# STM32H753_PINOUT.net
KiCad netlist of a schematic drawn in Altium Designer
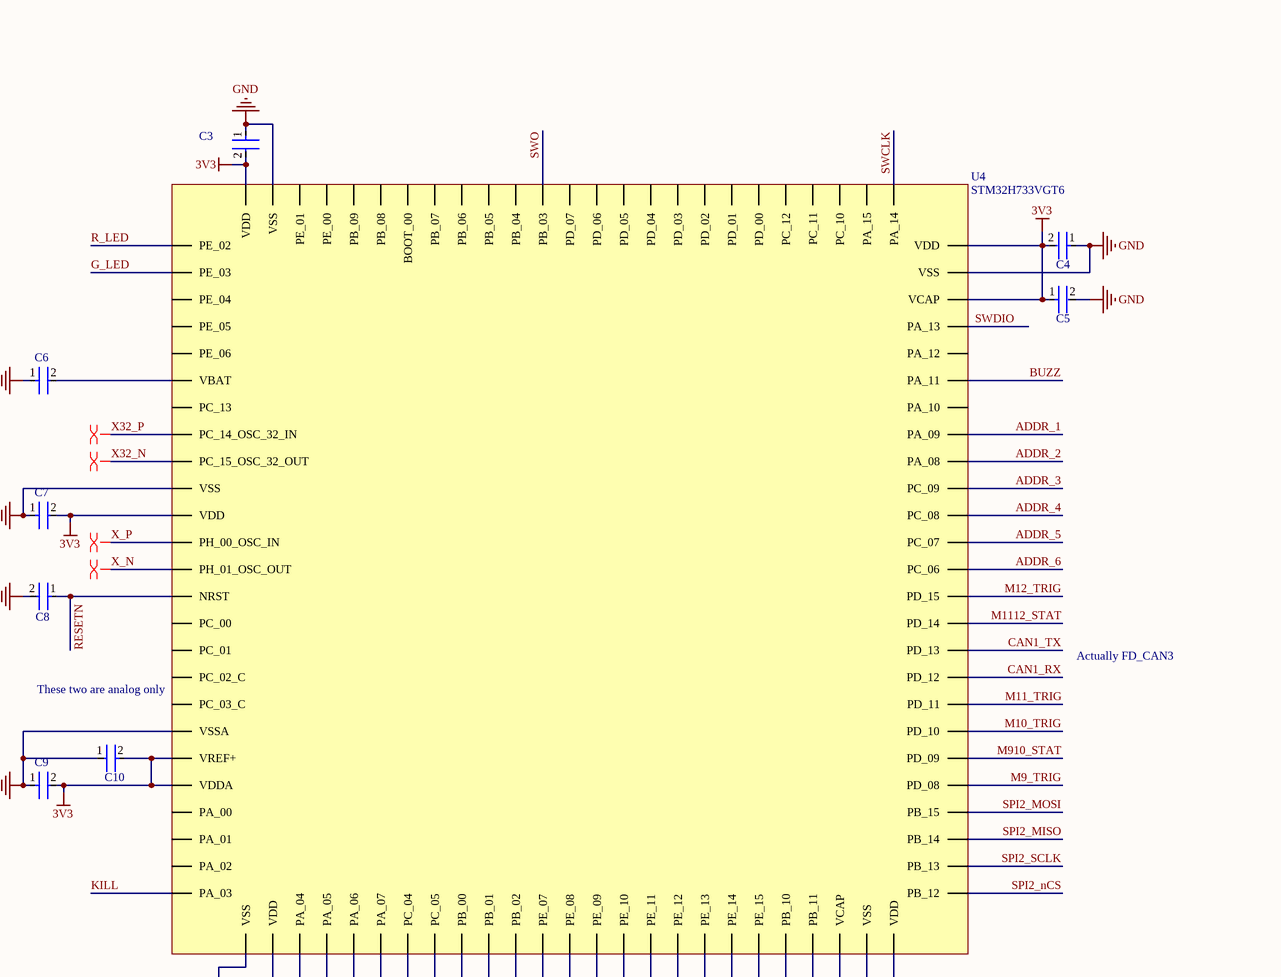
[diagram p0: STM32H753_PINOUT.SchDoc, top middle]
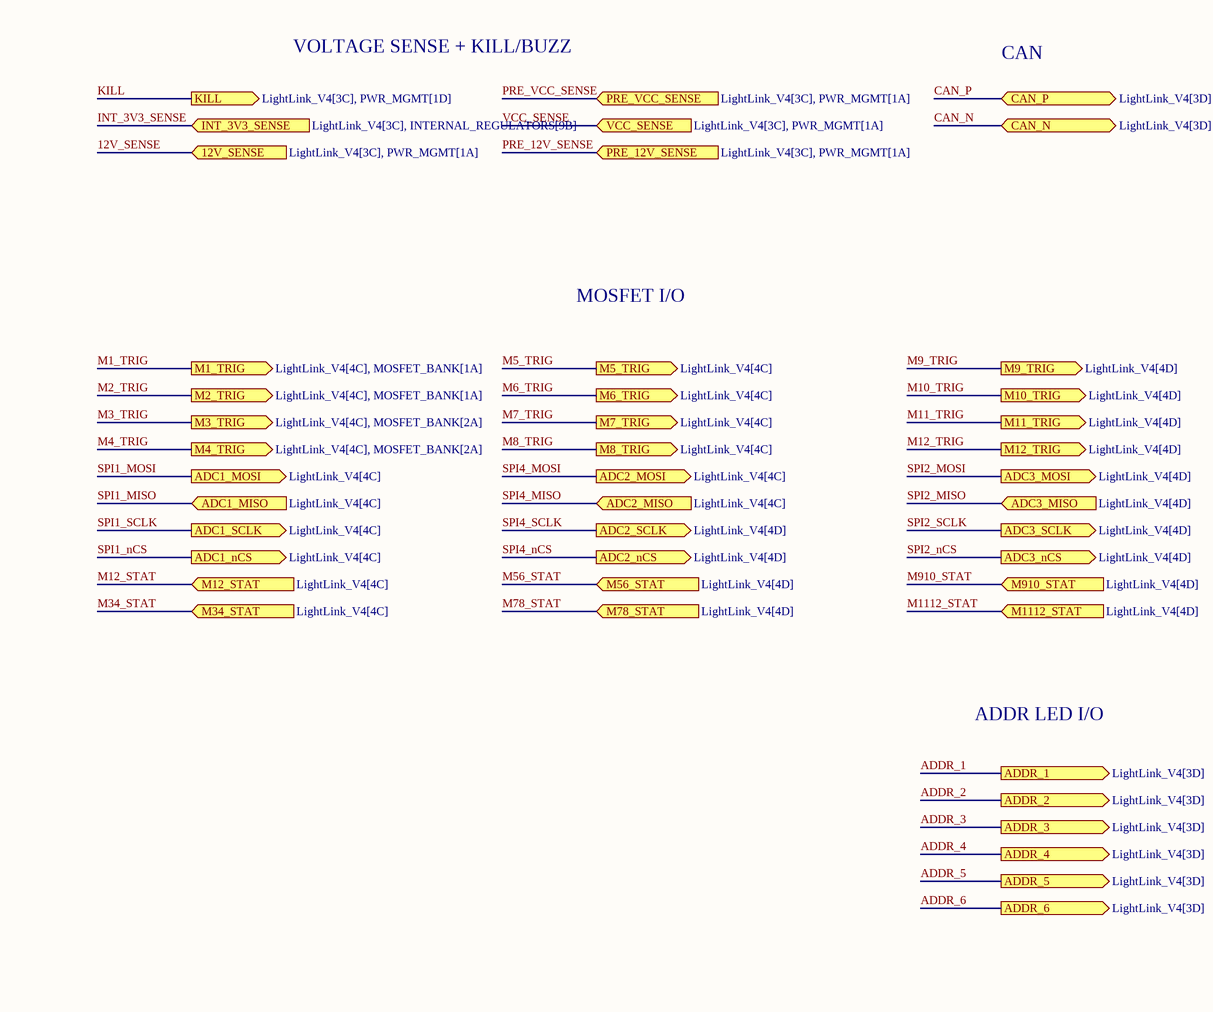
[diagram p1: STM32H753_PINOUT.SchDoc, top right]
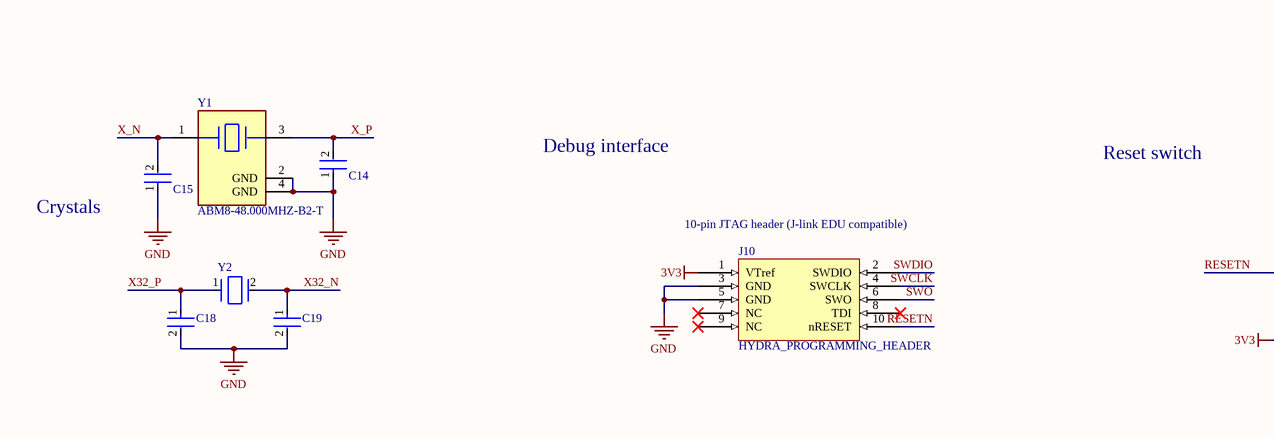
[diagram p2: STM32H753_PINOUT.SchDoc, bottom left]
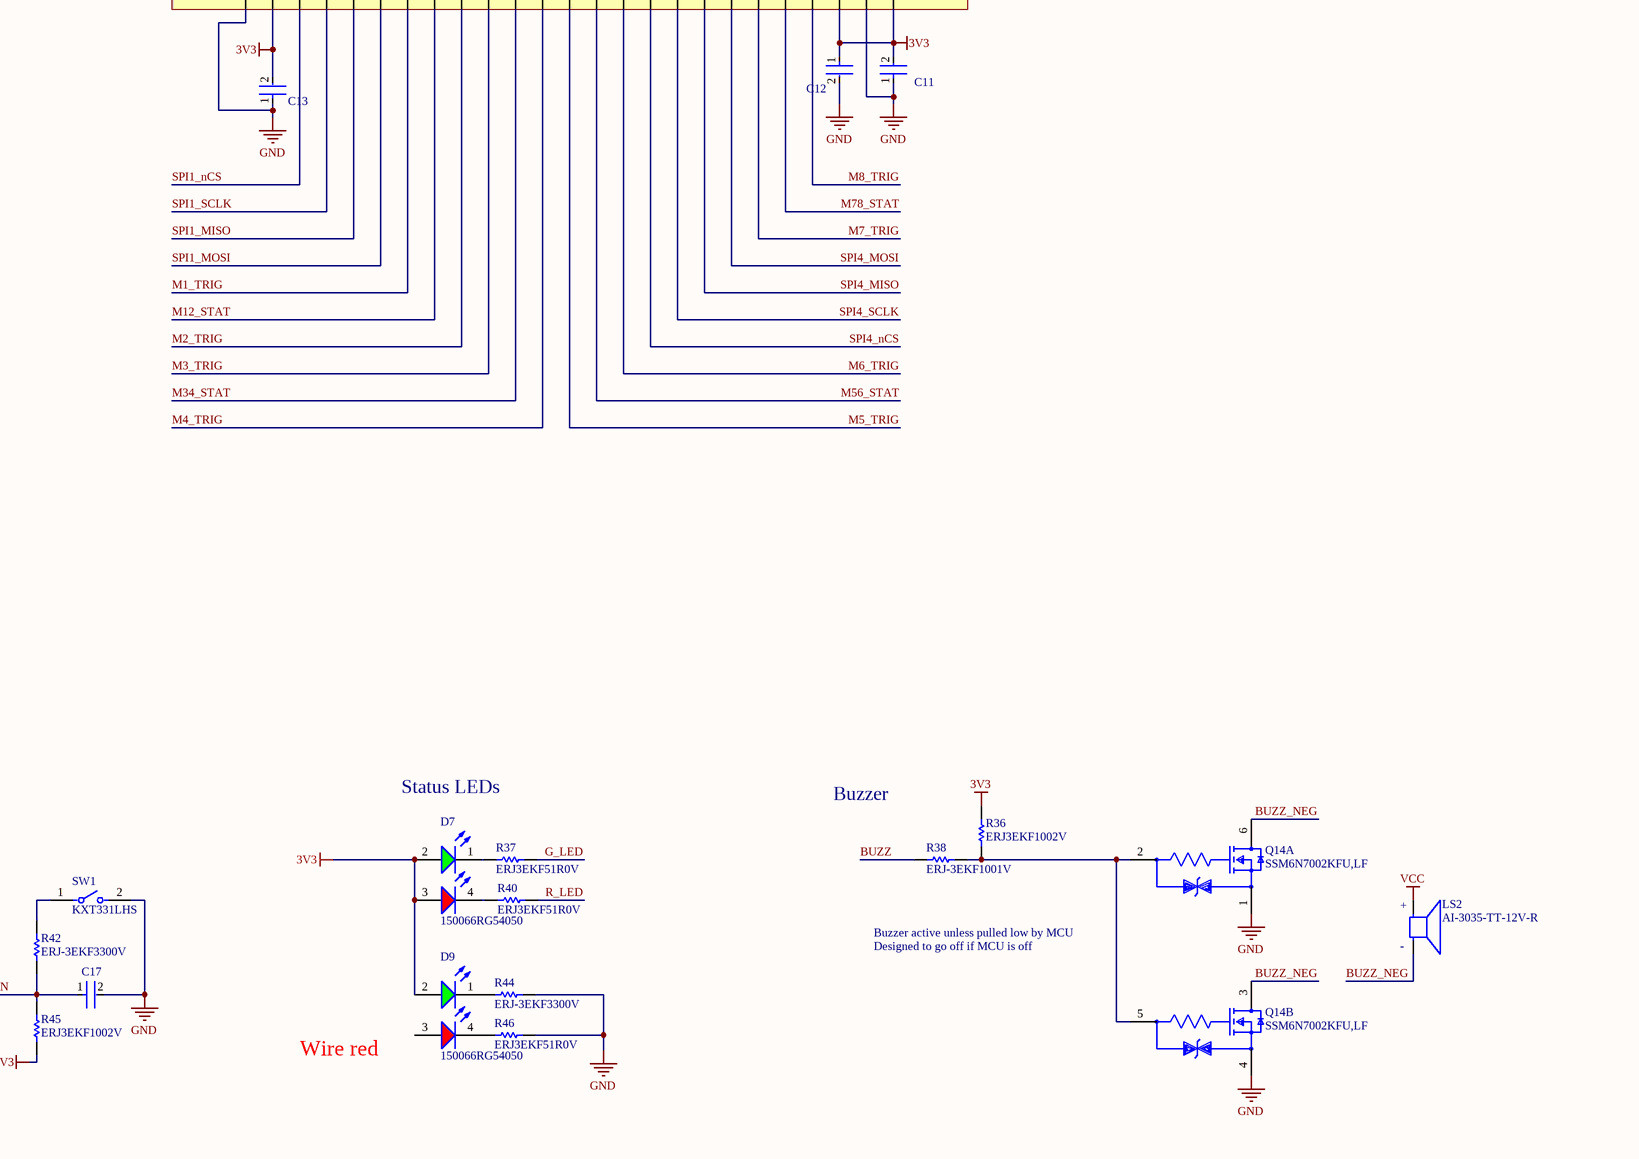
[diagram p3: STM32H753_PINOUT.SchDoc, bottom middle]
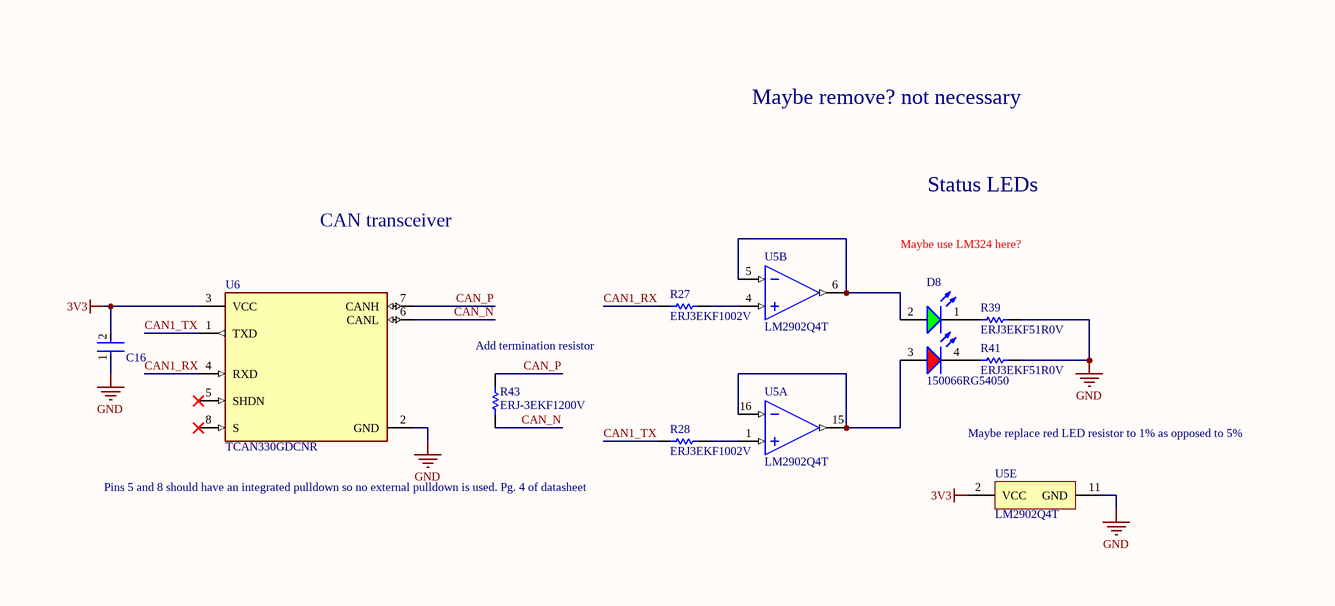
[diagram p4: STM32H753_PINOUT.SchDoc, bottom right]

(export (version "E")
  (design (tool "Eeschema 10.0.6"))
  (components
    (comp (ref "C3")
      (value "C0402C104K8PACTU")
      (footprint "FP-C0402-BB-MFG")
      (fields
        (field (name "MANUFACTURER") "Kemet")
        (field (name "TOLERANCE") "0.1")
        (field (name "OCTOPART") "https://octopart.com/c0402c104k8pactu-kemet-140039")
      )
      (libsource (lib "Altium Content Vault") (part "b4654b650e69147ec39a6b967a45e02"))
    )
    (comp (ref "C4")
      (value "C0402C104K8PACTU")
      (footprint "FP-C0402-BB-MFG")
      (fields
        (field (name "MANUFACTURER") "Kemet")
        (field (name "TOLERANCE") "0.1")
        (field (name "OCTOPART") "https://octopart.com/c0402c104k8pactu-kemet-140039")
      )
      (libsource (lib "Altium Content Vault") (part "b4654b650e69147ec39a6b967a45e02"))
    )
    (comp (ref "C5")
      (value "C1005X7S1A225K050BC")
      (footprint "FP-C1005-050-0_15-0_1-MFG")
      (description "CAP CER 2.2UF 10V X7S 0402")
      (fields (field (name "TOLERANCE") "10%"))
      (libsource (lib "Altium Content Vault") (part "b4654b650e69147ec39a6b967a45e02"))
    )
    (comp (ref "C6")
      (value "C0402C104K8PACTU")
      (footprint "FP-C0402-BB-MFG")
      (fields
        (field (name "MANUFACTURER") "Kemet")
        (field (name "TOLERANCE") "0.1")
        (field (name "OCTOPART") "https://octopart.com/c0402c104k8pactu-kemet-140039")
      )
      (libsource (lib "Altium Content Vault") (part "b4654b650e69147ec39a6b967a45e02"))
    )
    (comp (ref "C7")
      (value "C0402C104K8PACTU")
      (footprint "FP-C0402-BB-MFG")
      (fields
        (field (name "MANUFACTURER") "Kemet")
        (field (name "TOLERANCE") "0.1")
        (field (name "OCTOPART") "https://octopart.com/c0402c104k8pactu-kemet-140039")
      )
      (libsource (lib "Altium Content Vault") (part "b4654b650e69147ec39a6b967a45e02"))
    )
    (comp (ref "C8")
      (value "C0402C104K8PACTU")
      (footprint "FP-C0402-BB-MFG")
      (description "CAP CER 0.1UF 10V X5R 0402")
      (fields (field (name "MANUFACTURER") "Kemet") (field (name "TOLERANCE") "0.1"))
      (libsource (lib "Altium Content Vault") (part "b4654b650e69147ec39a6b967a45e02"))
    )
    (comp (ref "C9")
      (value "C0402C104K8PACTU")
      (footprint "FP-C0402-BB-MFG")
      (fields
        (field (name "MANUFACTURER") "Kemet")
        (field (name "TOLERANCE") "0.1")
        (field (name "OCTOPART") "https://octopart.com/c0402c104k8pactu-kemet-140039")
      )
      (libsource (lib "Altium Content Vault") (part "b4654b650e69147ec39a6b967a45e02"))
    )
    (comp (ref "C10")
      (value "GRM155R71C104KA88D")
      (footprint "FP-GRM15-MFG")
      (description "CAP CER 0.1UF 16V X7R 0402")
      (fields
        (field (name "TOLERANCE") "10%")
        (field (name "OCTOPART") "https://octopart.com/grm155r71c104ka88d-murata-196880")
      )
      (libsource (lib "Altium Content Vault") (part "236180d848d6139a670b325ea6854c9"))
    )
    (comp (ref "C11")
      (value "C0402C104K8PACTU")
      (footprint "FP-C0402-BB-MFG")
      (fields
        (field (name "MANUFACTURER") "Kemet")
        (field (name "TOLERANCE") "0.1")
        (field (name "OCTOPART") "https://octopart.com/c0402c104k8pactu-kemet-140039")
      )
      (libsource (lib "Altium Content Vault") (part "b4654b650e69147ec39a6b967a45e02"))
    )
    (comp (ref "C12")
      (value "C1005X7S1A225K050BC")
      (footprint "FP-C1005-050-0_15-0_1-MFG")
      (description "CAP CER 2.2UF 10V X7S 0402")
      (fields (field (name "TOLERANCE") "10%"))
      (libsource (lib "Altium Content Vault") (part "b4654b650e69147ec39a6b967a45e02"))
    )
    (comp (ref "C13")
      (value "C0402C104K8PACTU")
      (footprint "FP-C0402-BB-MFG")
      (fields
        (field (name "MANUFACTURER") "Kemet")
        (field (name "TOLERANCE") "0.1")
        (field (name "OCTOPART") "https://octopart.com/c0402c104k8pactu-kemet-140039")
      )
      (libsource (lib "Altium Content Vault") (part "b4654b650e69147ec39a6b967a45e02"))
    )
    (comp (ref "C14")
      (value "08051A6R8CAT2A")
      (footprint "FP-0805-L_2_01_0_2-W_1_25-MFG")
      (description "General Purpose Ceramic Capacitor, 0805, 6.8pF, 0.25pF, C0G, 30ppm/°C, 100V")
      (fields (field (name "VOLTAGE") "100V") (field (name "TOLERANCE") "5%"))
      (libsource (lib "Altium Content Vault") (part "02cd4be3c70576c341d710602a673aa"))
    )
    (comp (ref "C15")
      (value "08051A6R8CAT2A")
      (footprint "FP-0805-L_2_01_0_2-W_1_25-MFG")
      (description "General Purpose Ceramic Capacitor, 0805, 6.8pF, 0.25pF, C0G, 30ppm/°C, 100V")
      (fields (field (name "VOLTAGE") "100V") (field (name "TOLERANCE") "5%"))
      (libsource (lib "Altium Content Vault") (part "02cd4be3c70576c341d710602a673aa"))
    )
    (comp (ref "C16")
      (value "C0402C104K8PACTU")
      (footprint "FP-C0402-BB-MFG")
      (description "CAP CER 0.1UF 10V X5R 0402")
      (fields (field (name "MANUFACTURER") "Kemet") (field (name "TOLERANCE") "0.1"))
      (libsource (lib "Altium Content Vault") (part "b4654b650e69147ec39a6b967a45e02"))
    )
    (comp (ref "C17")
      (value "C0402C104K8PACTU")
      (footprint "FP-C0402-BB-MFG")
      (description "CAP CER 0.1UF 10V X5R 0402")
      (fields (field (name "MANUFACTURER") "Kemet") (field (name "TOLERANCE") "0.1"))
      (libsource (lib "Altium Content Vault") (part "b4654b650e69147ec39a6b967a45e02"))
    )
    (comp (ref "C18")
      (value "C0805C180J5GACTU")
      (footprint "FP-C0805C-DN-MFG")
      (description "CAP CER 18PF 50V C0G/NP0 0805")
      (fields
        (field (name "OCTOPART") "https://octopart.com/c0805c180j5gactu-kemet-144810")
        (field (name "TOLERANCE") "0.05")
      )
      (libsource (lib "Altium Content Vault") (part "b4654b650e69147ec39a6b967a45e02"))
    )
    (comp (ref "C19")
      (value "C0805C180J5GACTU")
      (footprint "FP-C0805C-DN-MFG")
      (description "CAP CER 18PF 50V C0G/NP0 0805")
      (fields
        (field (name "OCTOPART") "https://octopart.com/c0805c180j5gactu-kemet-144810")
        (field (name "TOLERANCE") "0.05")
      )
      (libsource (lib "Altium Content Vault") (part "b4654b650e69147ec39a6b967a45e02"))
    )
    (comp (ref "D7")
      (value "150066RG54050")
      (footprint "WL-SBCD_0606")
      (description "Led, Red/Grn, 180Mcd/230Mcd, 624Nm/525Nm Rohs Compliant: Yes")
      (libsource (lib "uORocketry Hardware") (part "WL-SBCD_0606_Red & Green"))
    )
    (comp (ref "D8")
      (value "150066RG54050")
      (footprint "WL-SBCD_0606")
      (description "Led, Red/Grn, 180Mcd/230Mcd, 624Nm/525Nm Rohs Compliant: Yes")
      (libsource (lib "uORocketry Hardware") (part "WL-SBCD_0606_Red & Green"))
    )
    (comp (ref "D9")
      (value "150066RG54050")
      (footprint "WL-SBCD_0606")
      (description "Led, Red/Grn, 180Mcd/230Mcd, 624Nm/525Nm Rohs Compliant: Yes")
      (libsource (lib "uORocketry Hardware") (part "WL-SBCD_0606_Red & Green"))
    )
    (comp (ref "J10")
      (value "HYDRA_PROGRAMMING_HEADER")
      (footprint "3220-10-0300-00-Footprint-1")
      (description "CONN HEADER SMD 10POS 1.27MM (specifically compatible with J-Link EDU cable) PN: 3220-10-0300-00")
      (libsource (lib "uORocketry Hardware") (part "3220-10-0300-00-Symbol-1"))
    )
    (comp (ref "LS2")
      (value "AI-3035-TT-12V-R")
      (footprint "AI-3035-TT-12V-R-Footprint-1")
      (description "Audio Indicator 12V 12mA 110dBA 3.5KHz Resonant Frequency Thru-Hole")
      (libsource (lib "uORocketry Hardware") (part "AI-3035-TT-12V-R"))
    )
    (comp (ref "Q14")
      (value "SSM6N7002KFU,LF")
      (footprint "FP-SSOP6-P-0_65A-MFG")
      (description "MOSFET 2N-CH 60V 0.3A")
      (libsource (lib "Altium Content Vault") (part "088aa6ac103fdeebe0d1c52ece6b7b9"))
    )
    (comp (ref "R27")
      (value "ERJ3EKF1002V")
      (footprint "RESC1609X55X30LL15T15")
      (description "Chip Resistor, 10 KOhm, +/- 1%, 0.1 W, -55 to 155 degC, 0603 (1608 Metric), RoHS, Tape and Reel")
      (fields (field (name "TOLERANCE") "1%") (field (name "MANUFACTURER") "Panasonic"))
      (libsource (lib "Altium Content Vault") (part "RES-2"))
    )
    (comp (ref "R28")
      (value "ERJ3EKF1002V")
      (footprint "RESC1609X55X30LL15T15")
      (description "Chip Resistor, 10 KOhm, +/- 1%, 0.1 W, -55 to 155 degC, 0603 (1608 Metric), RoHS, Tape and Reel")
      (fields (field (name "TOLERANCE") "1%") (field (name "MANUFACTURER") "Panasonic"))
      (libsource (lib "Altium Content Vault") (part "RES-2"))
    )
    (comp (ref "R36")
      (value "ERJ3EKF1002V")
      (footprint "RESC1609X55X30LL15T15")
      (description "Chip Resistor, 10 KOhm, +/- 1%, 0.1 W, -55 to 155 degC, 0603 (1608 Metric), RoHS, Tape and Reel")
      (fields (field (name "TOLERANCE") "1%") (field (name "MANUFACTURER") "Panasonic"))
      (libsource (lib "Altium Content Vault") (part "RES-2"))
    )
    (comp (ref "R37")
      (value "ERJ3EKF51R0V")
      (footprint "RESC1608X55X30NL15T15")
      (fields (field (name "MANUFACTURER") "Panasonic"))
      (libsource (lib "Altium Content Vault") (part "RES"))
    )
    (comp (ref "R38")
      (value "ERJ-3EKF1001V")
      (footprint "RESC1608X55X30LL15T15")
      (fields (field (name "MANUFACTURER") "Panasonic"))
      (libsource (lib "Altium Content Vault") (part "RES"))
    )
    (comp (ref "R39")
      (value "ERJ3EKF51R0V")
      (footprint "RESC1608X55X30NL15T15")
      (fields (field (name "MANUFACTURER") "Panasonic"))
      (libsource (lib "Altium Content Vault") (part "RES"))
    )
    (comp (ref "R40")
      (value "ERJ3EKF51R0V")
      (footprint "RESC1608X55X30NL15T15")
      (fields (field (name "MANUFACTURER") "Panasonic"))
      (libsource (lib "Altium Content Vault") (part "RES"))
    )
    (comp (ref "R41")
      (value "ERJ3EKF51R0V")
      (footprint "RESC1608X55X30NL15T15")
      (fields (field (name "MANUFACTURER") "Panasonic"))
      (libsource (lib "Altium Content Vault") (part "RES"))
    )
    (comp (ref "R42")
      (value "ERJ-3EKF3300V")
      (footprint "RESC1608X55X30LL15T15")
      (description "Chip Resistor, 330 Ohm, +/- 1%, 0.1 W, -55 to 155 degC, 0603 (1608 Metric), RoHS, Tape and Reel")
      (libsource (lib "Altium Content Vault") (part "RES-2"))
    )
    (comp (ref "R43")
      (value "ERJ-3EKF1200V")
      (footprint "RESC1609X55X30ML15T15")
      (description "Chip Resistor, 120 Ohm, +/- 1%, 0.1 W, -55 to 155 degC, 0603 (1608 Metric), RoHS, Tape and Reel")
      (fields (field (name "TOLERANCE") "1%") (field (name "MANUFACTURER") "Panasonic"))
      (libsource (lib "Altium Content Vault") (part "RES-2"))
    )
    (comp (ref "R44")
      (value "ERJ-3EKF3300V")
      (footprint "RESC1608X55X30LL15T15")
      (description "Chip Resistor, 330 Ohm, +/- 1%, 0.1 W, -55 to 155 degC, 0603 (1608 Metric), RoHS, Tape and Reel")
      (libsource (lib "Altium Content Vault") (part "RES-2"))
    )
    (comp (ref "R45")
      (value "ERJ3EKF1002V")
      (footprint "RESC1609X55X30LL15T15")
      (description "Chip Resistor, 10 KOhm, +/- 1%, 0.1 W, -55 to 155 degC, 0603 (1608 Metric), RoHS, Tape and Reel")
      (fields (field (name "TOLERANCE") "1%") (field (name "MANUFACTURER") "Panasonic"))
      (libsource (lib "Altium Content Vault") (part "RES-2"))
    )
    (comp (ref "R46")
      (value "ERJ3EKF51R0V")
      (footprint "RESC1608X55X30NL15T15")
      (fields (field (name "MANUFACTURER") "Panasonic"))
      (libsource (lib "Altium Content Vault") (part "RES"))
    )
    (comp (ref "SW1")
      (value "KXT331LHS")
      (footprint "FP-KXT331LHS-MFG")
      (description "SWITCH TACTILE SPST-NO 0.02A 15V")
      (libsource (lib "Altium Content Vault") (part "bb27bde45df87f1f469753f287ef5ae"))
    )
    (comp (ref "U4")
      (value "STM32H733VGT6")
      (footprint "STM32H733VGT6-Footprint-1")
      (description "MCU 32-bit ARM Cortex M7 RISC 1MB Flash 1.8V/2.5V/3.3V 100-Pin LQFP Tray")
      (libsource (lib "uORocketry Hardware") (part "STM32H733VGT6"))
    )
    (comp (ref "U5")
      (value "LM2902Q4T")
      (footprint "LM2902Q4T-Footprint-1")
      (description "LM2902 Series 30 V 1.3 MHz Low-Power Quad Operational Amplifier - QFN-16 (3x3)")
      (libsource (lib "uORocketry Hardware") (part "LM2902Q4T"))
    )
    (comp (ref "U6")
      (value "TCAN330GDCNR")
      (footprint "FP-DCN0008A-MFG")
      (description "IC TRANSCEIVER 1/1 SOT23-8")
      (libsource (lib "Altium Content Vault") (part "22681b49c22ad38c6a4e12e04c36c7a"))
    )
    (comp (ref "Y1")
      (value "ABM8-48.000MHZ-B2-T")
      (footprint "FP-ABM8-MFG")
      (description "Crystal 48MHz ±20ppm 18pF SMD-4 3.2mm x 2.5mm")
      (fields (field (name "TOLERANCE") "20ppm"))
      (libsource (lib "Altium Content Vault") (part "dfdb7f9a12507849fb681da9a70121c"))
    )
    (comp (ref "Y2")
      (value "ECS-.327-12.5-1210-TR")
      (footprint "FP-ECX-1210-MFG")
      (description "CRYSTAL 32.7680KHZ 12.5PF SMD")
      (fields
        (field (name "OCTOPART") "https://octopart.com/ecs-.327-12.5-1210-tr-ecs+international-81221340")
        (field (name "TOLERANCE") "20ppm")
      )
      (libsource (lib "Altium Content Vault") (part "99724985039315a44fd0d1401b84e49"))
    )
  )
  (nets
    (net (code "2") (name "/ADDR_1") (class "Default")
      (node (ref "U4") (pin "68") (pinfunction "PA_09_68") (pintype "passive"))
    )
    (net (code "3") (name "/ADDR_2") (class "Default")
      (node (ref "U4") (pin "67") (pinfunction "PA_08_67") (pintype "passive"))
    )
    (net (code "4") (name "/ADDR_3") (class "Default")
      (node (ref "U4") (pin "66") (pinfunction "PC_09_66") (pintype "passive"))
    )
    (net (code "5") (name "/ADDR_4") (class "Default")
      (node (ref "U4") (pin "65") (pinfunction "PC_08_65") (pintype "passive"))
    )
    (net (code "6") (name "/ADDR_5") (class "Default")
      (node (ref "U4") (pin "64") (pinfunction "PC_07_64") (pintype "passive"))
    )
    (net (code "7") (name "/ADDR_6") (class "Default")
      (node (ref "U4") (pin "63") (pinfunction "PC_06_63") (pintype "passive"))
    )
    (net (code "8") (name "/BUZZ") (class "Default")
      (node (ref "R38") (pin "1") (pinfunction "1_1") (pintype "passive"))
      (node (ref "U4") (pin "70") (pinfunction "PA_11_70") (pintype "passive"))
    )
    (net (code "9") (name "/BUZZ_NEG") (class "Default")
      (node (ref "LS2") (pin "N") (pinfunction "N_N") (pintype "passive"))
      (node (ref "Q14") (pin "3") (pinfunction "Drain2_3") (pintype "passive"))
      (node (ref "Q14") (pin "6") (pinfunction "Drain1_6") (pintype "passive"))
    )
    (net (code "10") (name "/CAN1_RX") (class "Default")
      (node (ref "R27") (pin "1") (pinfunction "1_1") (pintype "passive"))
      (node (ref "U4") (pin "59") (pinfunction "PD_12_59") (pintype "passive"))
      (node (ref "U6") (pin "4") (pinfunction "RXD_4") (pintype "input"))
    )
    (net (code "11") (name "/CAN1_TX") (class "Default")
      (node (ref "R28") (pin "1") (pinfunction "1_1") (pintype "passive"))
      (node (ref "U4") (pin "60") (pinfunction "PD_13_60") (pintype "passive"))
      (node (ref "U6") (pin "1") (pinfunction "TXD_1") (pintype "output"))
    )
    (net (code "12") (name "/CAN_N") (class "Default")
      (node (ref "R43") (pin "1") (pinfunction "1_1") (pintype "passive"))
      (node (ref "U6") (pin "6") (pinfunction "CANL_6") (pintype "bidirectional"))
    )
    (net (code "13") (name "/CAN_P") (class "Default")
      (node (ref "R43") (pin "2") (pinfunction "2_2") (pintype "passive"))
      (node (ref "U6") (pin "7") (pinfunction "CANH_7") (pintype "bidirectional"))
    )
    (net (code "14") (name "/G_LED") (class "Default")
      (node (ref "R37") (pin "2") (pinfunction "2_2") (pintype "passive"))
      (node (ref "U4") (pin "2") (pinfunction "PE_03_2") (pintype "passive"))
    )
    (net (code "16") (name "/KILL") (class "Default")
      (node (ref "U4") (pin "25") (pinfunction "PA_03_25") (pintype "passive"))
    )
    (net (code "17") (name "/M1_TRIG") (class "Default")
      (node (ref "U4") (pin "32") (pinfunction "PC_04_32") (pintype "passive"))
    )
    (net (code "18") (name "/M2_TRIG") (class "Default")
      (node (ref "U4") (pin "34") (pinfunction "PB_00_34") (pintype "passive"))
    )
    (net (code "19") (name "/M3_TRIG") (class "Default")
      (node (ref "U4") (pin "35") (pinfunction "PB_01_35") (pintype "passive"))
    )
    (net (code "20") (name "/M4_TRIG") (class "Default")
      (node (ref "U4") (pin "37") (pinfunction "PE_07_37") (pintype "passive"))
    )
    (net (code "21") (name "/M5_TRIG") (class "Default")
      (node (ref "U4") (pin "38") (pinfunction "PE_08_38") (pintype "passive"))
    )
    (net (code "22") (name "/M6_TRIG") (class "Default")
      (node (ref "U4") (pin "40") (pinfunction "PE_10_40") (pintype "passive"))
    )
    (net (code "23") (name "/M7_TRIG") (class "Default")
      (node (ref "U4") (pin "45") (pinfunction "PE_15_45") (pintype "passive"))
    )
    (net (code "24") (name "/M8_TRIG") (class "Default")
      (node (ref "U4") (pin "47") (pinfunction "PB_11_47") (pintype "passive"))
    )
    (net (code "25") (name "/M9_TRIG") (class "Default")
      (node (ref "U4") (pin "55") (pinfunction "PD_08_55") (pintype "passive"))
    )
    (net (code "26") (name "/M10_TRIG") (class "Default")
      (node (ref "U4") (pin "57") (pinfunction "PD_10_57") (pintype "passive"))
    )
    (net (code "27") (name "/M11_TRIG") (class "Default")
      (node (ref "U4") (pin "58") (pinfunction "PD_11_58") (pintype "passive"))
    )
    (net (code "28") (name "/M12_STAT") (class "Default")
      (node (ref "U4") (pin "33") (pinfunction "PC_05_33") (pintype "passive"))
    )
    (net (code "29") (name "/M12_TRIG") (class "Default")
      (node (ref "U4") (pin "62") (pinfunction "PD_15_62") (pintype "passive"))
    )
    (net (code "30") (name "/M34_STAT") (class "Default")
      (node (ref "U4") (pin "36") (pinfunction "PB_02_36") (pintype "passive"))
    )
    (net (code "31") (name "/M56_STAT") (class "Default")
      (node (ref "U4") (pin "39") (pinfunction "PE_09_39") (pintype "passive"))
    )
    (net (code "32") (name "/M78_STAT") (class "Default")
      (node (ref "U4") (pin "46") (pinfunction "PB_10_46") (pintype "passive"))
    )
    (net (code "33") (name "/M910_STAT") (class "Default")
      (node (ref "U4") (pin "56") (pinfunction "PD_09_56") (pintype "passive"))
    )
    (net (code "34") (name "/M1112_STAT") (class "Default")
      (node (ref "U4") (pin "61") (pinfunction "PD_14_61") (pintype "passive"))
    )
    (net (code "37") (name "/RESETN") (class "Default")
      (node (ref "C17") (pin "1") (pinfunction "1_1") (pintype "passive"))
      (node (ref "C8") (pin "1") (pinfunction "1_1") (pintype "passive"))
      (node (ref "J10") (pin "10") (pinfunction "nRESET_10") (pintype "input"))
      (node (ref "R42") (pin "1") (pinfunction "1_1") (pintype "passive"))
      (node (ref "R45") (pin "2") (pinfunction "2_2") (pintype "passive"))
      (node (ref "U4") (pin "14") (pinfunction "NRST_14") (pintype "passive"))
    )
    (net (code "38") (name "/R_LED") (class "Default")
      (node (ref "R40") (pin "2") (pinfunction "2_2") (pintype "passive"))
      (node (ref "U4") (pin "1") (pinfunction "PE_02_1") (pintype "passive"))
    )
    (net (code "39") (name "/SPI1_MISO") (class "Default")
      (node (ref "U4") (pin "30") (pinfunction "PA_06_30") (pintype "passive"))
    )
    (net (code "40") (name "/SPI1_MOSI") (class "Default")
      (node (ref "U4") (pin "31") (pinfunction "PA_07_31") (pintype "passive"))
    )
    (net (code "41") (name "/SPI1_SCLK") (class "Default")
      (node (ref "U4") (pin "29") (pinfunction "PA_05_29") (pintype "passive"))
    )
    (net (code "42") (name "/SPI1_nCS") (class "Default")
      (node (ref "U4") (pin "28") (pinfunction "PA_04_28") (pintype "passive"))
    )
    (net (code "43") (name "/SPI2_MISO") (class "Default")
      (node (ref "U4") (pin "53") (pinfunction "PB_14_53") (pintype "passive"))
    )
    (net (code "44") (name "/SPI2_MOSI") (class "Default")
      (node (ref "U4") (pin "54") (pinfunction "PB_15_54") (pintype "passive"))
    )
    (net (code "45") (name "/SPI2_SCLK") (class "Default")
      (node (ref "U4") (pin "52") (pinfunction "PB_13_52") (pintype "passive"))
    )
    (net (code "46") (name "/SPI2_nCS") (class "Default")
      (node (ref "U4") (pin "51") (pinfunction "PB_12_51") (pintype "passive"))
    )
    (net (code "47") (name "/SPI4_MISO") (class "Default")
      (node (ref "U4") (pin "43") (pinfunction "PE_13_43") (pintype "passive"))
    )
    (net (code "48") (name "/SPI4_MOSI") (class "Default")
      (node (ref "U4") (pin "44") (pinfunction "PE_14_44") (pintype "passive"))
    )
    (net (code "49") (name "/SPI4_SCLK") (class "Default")
      (node (ref "U4") (pin "42") (pinfunction "PE_12_42") (pintype "passive"))
    )
    (net (code "50") (name "/SPI4_nCS") (class "Default")
      (node (ref "U4") (pin "41") (pinfunction "PE_11_41") (pintype "passive"))
    )
    (net (code "51") (name "/SWCLK") (class "Default")
      (node (ref "J10") (pin "4") (pinfunction "SWCLK_4") (pintype "input"))
      (node (ref "U4") (pin "76") (pinfunction "PA_14_76") (pintype "passive"))
    )
    (net (code "52") (name "/SWDIO") (class "Default")
      (node (ref "J10") (pin "2") (pinfunction "SWDIO_2") (pintype "input"))
      (node (ref "U4") (pin "72") (pinfunction "PA_13_72") (pintype "passive"))
    )
    (net (code "53") (name "/SWO") (class "Default")
      (node (ref "J10") (pin "6") (pinfunction "SWO_6") (pintype "input"))
      (node (ref "U4") (pin "89") (pinfunction "PB_03_89") (pintype "passive"))
    )
    (net (code "55") (name "/X32_N") (class "Default")
      (node (ref "C19") (pin "1") (pinfunction "1_1") (pintype "passive"))
      (node (ref "U4") (pin "9") (pinfunction "PC_15_OSC_32_OUT_9") (pintype "passive"))
      (node (ref "Y2") (pin "2") (pinfunction "Out/In_2") (pintype "passive"))
    )
    (net (code "56") (name "/X32_P") (class "Default")
      (node (ref "C18") (pin "1") (pinfunction "1_1") (pintype "passive"))
      (node (ref "U4") (pin "8") (pinfunction "PC_14_OSC_32_IN_8") (pintype "passive"))
      (node (ref "Y2") (pin "1") (pinfunction "In/Out_1") (pintype "passive"))
    )
    (net (code "57") (name "/X_N") (class "Default")
      (node (ref "C15") (pin "2") (pinfunction "2_2") (pintype "passive"))
      (node (ref "U4") (pin "13") (pinfunction "PH_01_OSC_OUT_13") (pintype "passive"))
      (node (ref "Y1") (pin "1") (pinfunction "1_1") (pintype "passive"))
    )
    (net (code "58") (name "/X_P") (class "Default")
      (node (ref "C14") (pin "2") (pinfunction "2_2") (pintype "passive"))
      (node (ref "U4") (pin "12") (pinfunction "PH_00_OSC_IN_12") (pintype "passive"))
      (node (ref "Y1") (pin "3") (pinfunction "3_3") (pintype "passive"))
    )
    (net (code "59") (name "3V3") (class "Default")
      (node (ref "C10") (pin "2") (pinfunction "2_2") (pintype "passive"))
      (node (ref "C11") (pin "2") (pinfunction "2_2") (pintype "passive"))
      (node (ref "C12") (pin "1") (pinfunction "1_1") (pintype "passive"))
      (node (ref "C13") (pin "2") (pinfunction "2_2") (pintype "passive"))
      (node (ref "C16") (pin "2") (pinfunction "2_2") (pintype "passive"))
      (node (ref "C3") (pin "2") (pinfunction "2_2") (pintype "passive"))
      (node (ref "C4") (pin "2") (pinfunction "2_2") (pintype "passive"))
      (node (ref "C5") (pin "1") (pinfunction "1_1") (pintype "passive"))
      (node (ref "C7") (pin "2") (pinfunction "2_2") (pintype "passive"))
      (node (ref "C9") (pin "2") (pinfunction "2_2") (pintype "passive"))
      (node (ref "D7") (pin "2") (pinfunction "A_2") (pintype "passive"))
      (node (ref "D7") (pin "3") (pinfunction "A_3") (pintype "passive"))
      (node (ref "D9") (pin "2") (pinfunction "A_2") (pintype "passive"))
      (node (ref "J10") (pin "1") (pinfunction "VTref_1") (pintype "input"))
      (node (ref "R36") (pin "2") (pinfunction "2_2") (pintype "passive"))
      (node (ref "R45") (pin "1") (pinfunction "1_1") (pintype "passive"))
      (node (ref "U4") (pin "100") (pinfunction "VDD_100") (pintype "passive"))
      (node (ref "U4") (pin "11") (pinfunction "VDD_11") (pintype "passive"))
      (node (ref "U4") (pin "20") (pinfunction "VREF+_20") (pintype "passive"))
      (node (ref "U4") (pin "21") (pinfunction "VDDA_21") (pintype "passive"))
      (node (ref "U4") (pin "27") (pinfunction "VDD_27") (pintype "passive"))
      (node (ref "U4") (pin "48") (pinfunction "VCAP_48") (pintype "passive"))
      (node (ref "U4") (pin "50") (pinfunction "VDD_50") (pintype "passive"))
      (node (ref "U4") (pin "73") (pinfunction "VCAP_73") (pintype "passive"))
      (node (ref "U4") (pin "75") (pinfunction "VDD_75") (pintype "passive"))
      (node (ref "U5") (pin "2") (pinfunction "VCC_2") (pintype "power_in"))
      (node (ref "U6") (pin "3") (pinfunction "VCC_3") (pintype "power_in"))
    )
    (net (code "60") (name "GND") (class "Default")
      (node (ref "C10") (pin "1") (pinfunction "1_1") (pintype "passive"))
      (node (ref "C11") (pin "1") (pinfunction "1_1") (pintype "passive"))
      (node (ref "C12") (pin "2") (pinfunction "2_2") (pintype "passive"))
      (node (ref "C13") (pin "1") (pinfunction "1_1") (pintype "passive"))
      (node (ref "C14") (pin "1") (pinfunction "1_1") (pintype "passive"))
      (node (ref "C15") (pin "1") (pinfunction "1_1") (pintype "passive"))
      (node (ref "C16") (pin "1") (pinfunction "1_1") (pintype "passive"))
      (node (ref "C17") (pin "2") (pinfunction "2_2") (pintype "passive"))
      (node (ref "C18") (pin "2") (pinfunction "2_2") (pintype "passive"))
      (node (ref "C19") (pin "2") (pinfunction "2_2") (pintype "passive"))
      (node (ref "C3") (pin "1") (pinfunction "1_1") (pintype "passive"))
      (node (ref "C4") (pin "1") (pinfunction "1_1") (pintype "passive"))
      (node (ref "C5") (pin "2") (pinfunction "2_2") (pintype "passive"))
      (node (ref "C6") (pin "1") (pinfunction "1_1") (pintype "passive"))
      (node (ref "C7") (pin "1") (pinfunction "1_1") (pintype "passive"))
      (node (ref "C8") (pin "2") (pinfunction "2_2") (pintype "passive"))
      (node (ref "C9") (pin "1") (pinfunction "1_1") (pintype "passive"))
      (node (ref "J10") (pin "3") (pinfunction "GND_3") (pintype "input"))
      (node (ref "J10") (pin "5") (pinfunction "GND_5") (pintype "input"))
      (node (ref "Q14") (pin "1") (pinfunction "Source1_1") (pintype "passive"))
      (node (ref "Q14") (pin "4") (pinfunction "Source2_4") (pintype "passive"))
      (node (ref "R39") (pin "2") (pinfunction "2_2") (pintype "passive"))
      (node (ref "R41") (pin "2") (pinfunction "2_2") (pintype "passive"))
      (node (ref "R44") (pin "2") (pinfunction "2_2") (pintype "passive"))
      (node (ref "R46") (pin "2") (pinfunction "2_2") (pintype "passive"))
      (node (ref "SW1") (pin "2") (pinfunction "2_2") (pintype "passive"))
      (node (ref "U4") (pin "10") (pinfunction "VSS_10") (pintype "passive"))
      (node (ref "U4") (pin "19") (pinfunction "VSSA_19") (pintype "passive"))
      (node (ref "U4") (pin "26") (pinfunction "VSS_26") (pintype "passive"))
      (node (ref "U4") (pin "49") (pinfunction "VSS_49") (pintype "passive"))
      (node (ref "U4") (pin "74") (pinfunction "VSS_74") (pintype "passive"))
      (node (ref "U4") (pin "99") (pinfunction "VSS_99") (pintype "passive"))
      (node (ref "U5") (pin "11") (pinfunction "GND_11") (pintype "power_in"))
      (node (ref "U6") (pin "2") (pinfunction "GND_2") (pintype "power_in"))
      (node (ref "Y1") (pin "2") (pinfunction "GND_2") (pintype "power_in"))
      (node (ref "Y1") (pin "4") (pinfunction "GND_4") (pintype "power_in"))
    )
    (net (code "61") (name "Net-(D7-K-Pad1)") (class "Default")
      (node (ref "D7") (pin "1") (pinfunction "K_1") (pintype "passive"))
      (node (ref "R37") (pin "1") (pinfunction "1_1") (pintype "passive"))
    )
    (net (code "62") (name "Net-(D7-K-Pad4)") (class "Default")
      (node (ref "D7") (pin "4") (pinfunction "K_4") (pintype "passive"))
      (node (ref "R40") (pin "1") (pinfunction "1_1") (pintype "passive"))
    )
    (net (code "63") (name "Net-(D8-K-Pad1)") (class "Default")
      (node (ref "D8") (pin "1") (pinfunction "K_1") (pintype "passive"))
      (node (ref "R39") (pin "1") (pinfunction "1_1") (pintype "passive"))
    )
    (net (code "64") (name "Net-(D8-K-Pad4)") (class "Default")
      (node (ref "D8") (pin "4") (pinfunction "K_4") (pintype "passive"))
      (node (ref "R41") (pin "1") (pinfunction "1_1") (pintype "passive"))
    )
    (net (code "65") (name "Net-(D9-K-Pad1)") (class "Default")
      (node (ref "D9") (pin "1") (pinfunction "K_1") (pintype "passive"))
      (node (ref "R44") (pin "1") (pinfunction "1_1") (pintype "passive"))
    )
    (net (code "66") (name "Net-(D9-K-Pad4)") (class "Default")
      (node (ref "D9") (pin "4") (pinfunction "K_4") (pintype "passive"))
      (node (ref "R46") (pin "1") (pinfunction "1_1") (pintype "passive"))
    )
    (net (code "67") (name "Net-(Q14A-Gate1)") (class "Default")
      (node (ref "Q14") (pin "2") (pinfunction "Gate1_2") (pintype "passive"))
      (node (ref "Q14") (pin "5") (pinfunction "Gate2_5") (pintype "passive"))
      (node (ref "R36") (pin "1") (pinfunction "1_1") (pintype "passive"))
      (node (ref "R38") (pin "2") (pinfunction "2_2") (pintype "passive"))
    )
    (net (code "68") (name "Net-(R42-Pad2)") (class "Default")
      (node (ref "R42") (pin "2") (pinfunction "2_2") (pintype "passive"))
      (node (ref "SW1") (pin "1") (pinfunction "1_1") (pintype "passive"))
    )
    (net (code "69") (name "Net-(U4-VBAT)") (class "Default")
      (node (ref "C6") (pin "2") (pinfunction "2_2") (pintype "passive"))
      (node (ref "U4") (pin "6") (pinfunction "VBAT_6") (pintype "passive"))
    )
    (net (code "70") (name "Net-(U5A-1IN+)") (class "Default")
      (node (ref "R28") (pin "2") (pinfunction "2_2") (pintype "passive"))
      (node (ref "U5") (pin "1") (pinfunction "1IN+_1") (pintype "input"))
    )
    (net (code "71") (name "Net-(U5A-1IN-)") (class "Default")
      (node (ref "D8") (pin "3") (pinfunction "A_3") (pintype "passive"))
      (node (ref "U5") (pin "15") (pinfunction "1OUT_15") (pintype "output"))
      (node (ref "U5") (pin "16") (pinfunction "1IN-_16") (pintype "input"))
    )
    (net (code "72") (name "Net-(U5B-2IN+)") (class "Default")
      (node (ref "R27") (pin "2") (pinfunction "2_2") (pintype "passive"))
      (node (ref "U5") (pin "4") (pinfunction "2IN+_4") (pintype "input"))
    )
    (net (code "73") (name "Net-(U5B-2IN-)") (class "Default")
      (node (ref "D8") (pin "2") (pinfunction "A_2") (pintype "passive"))
      (node (ref "U5") (pin "5") (pinfunction "2IN-_5") (pintype "input"))
      (node (ref "U5") (pin "6") (pinfunction "2OUT_6") (pintype "output"))
    )
    (net (code "74") (name "VCC") (class "Default")
      (node (ref "LS2") (pin "P") (pinfunction "P_P") (pintype "passive"))
    )
    (net (code "75") (name "unconnected-(D9-A-Pad3)") (class "Default")
      (node (ref "D9") (pin "3") (pinfunction "A_3") (pintype "passive"))
    )
    (net (code "76") (name "unconnected-(J10-NC-Pad7)") (class "Default")
      (node (ref "J10") (pin "7") (pinfunction "NC_7") (pintype "input+no_connect"))
    )
    (net (code "77") (name "unconnected-(J10-NC-Pad9)") (class "Default")
      (node (ref "J10") (pin "9") (pinfunction "NC_9") (pintype "input+no_connect"))
    )
    (net (code "78") (name "unconnected-(J10-TDI-Pad8)") (class "Default")
      (node (ref "J10") (pin "8") (pinfunction "TDI_8") (pintype "input+no_connect"))
    )
    (net (code "79") (name "unconnected-(U4-BOOT_00-Pad94)") (class "Default")
      (node (ref "U4") (pin "94") (pinfunction "BOOT_00_94") (pintype "passive"))
    )
    (net (code "80") (name "unconnected-(U4-PA_00-Pad22)") (class "Default")
      (node (ref "U4") (pin "22") (pinfunction "PA_00_22") (pintype "passive"))
    )
    (net (code "81") (name "unconnected-(U4-PA_01-Pad23)") (class "Default")
      (node (ref "U4") (pin "23") (pinfunction "PA_01_23") (pintype "passive"))
    )
    (net (code "82") (name "unconnected-(U4-PA_02-Pad24)") (class "Default")
      (node (ref "U4") (pin "24") (pinfunction "PA_02_24") (pintype "passive"))
    )
    (net (code "83") (name "unconnected-(U4-PA_10-Pad69)") (class "Default")
      (node (ref "U4") (pin "69") (pinfunction "PA_10_69") (pintype "passive"))
    )
    (net (code "84") (name "unconnected-(U4-PA_12-Pad71)") (class "Default")
      (node (ref "U4") (pin "71") (pinfunction "PA_12_71") (pintype "passive"))
    )
    (net (code "85") (name "unconnected-(U4-PA_15-Pad77)") (class "Default")
      (node (ref "U4") (pin "77") (pinfunction "PA_15_77") (pintype "passive"))
    )
    (net (code "86") (name "unconnected-(U4-PB_04-Pad90)") (class "Default")
      (node (ref "U4") (pin "90") (pinfunction "PB_04_90") (pintype "passive"))
    )
    (net (code "87") (name "unconnected-(U4-PB_05-Pad91)") (class "Default")
      (node (ref "U4") (pin "91") (pinfunction "PB_05_91") (pintype "passive"))
    )
    (net (code "88") (name "unconnected-(U4-PB_06-Pad92)") (class "Default")
      (node (ref "U4") (pin "92") (pinfunction "PB_06_92") (pintype "passive"))
    )
    (net (code "89") (name "unconnected-(U4-PB_07-Pad93)") (class "Default")
      (node (ref "U4") (pin "93") (pinfunction "PB_07_93") (pintype "passive"))
    )
    (net (code "90") (name "unconnected-(U4-PB_08-Pad95)") (class "Default")
      (node (ref "U4") (pin "95") (pinfunction "PB_08_95") (pintype "passive"))
    )
    (net (code "91") (name "unconnected-(U4-PB_09-Pad96)") (class "Default")
      (node (ref "U4") (pin "96") (pinfunction "PB_09_96") (pintype "passive"))
    )
    (net (code "92") (name "unconnected-(U4-PC_00-Pad15)") (class "Default")
      (node (ref "U4") (pin "15") (pinfunction "PC_00_15") (pintype "passive"))
    )
    (net (code "93") (name "unconnected-(U4-PC_01-Pad16)") (class "Default")
      (node (ref "U4") (pin "16") (pinfunction "PC_01_16") (pintype "passive"))
    )
    (net (code "94") (name "unconnected-(U4-PC_02_C-Pad17)") (class "Default")
      (node (ref "U4") (pin "17") (pinfunction "PC_02_C_17") (pintype "passive"))
    )
    (net (code "95") (name "unconnected-(U4-PC_03_C-Pad18)") (class "Default")
      (node (ref "U4") (pin "18") (pinfunction "PC_03_C_18") (pintype "passive"))
    )
    (net (code "96") (name "unconnected-(U4-PC_10-Pad78)") (class "Default")
      (node (ref "U4") (pin "78") (pinfunction "PC_10_78") (pintype "passive"))
    )
    (net (code "97") (name "unconnected-(U4-PC_11-Pad79)") (class "Default")
      (node (ref "U4") (pin "79") (pinfunction "PC_11_79") (pintype "passive"))
    )
    (net (code "98") (name "unconnected-(U4-PC_12-Pad80)") (class "Default")
      (node (ref "U4") (pin "80") (pinfunction "PC_12_80") (pintype "passive"))
    )
    (net (code "99") (name "unconnected-(U4-PC_13-Pad7)") (class "Default")
      (node (ref "U4") (pin "7") (pinfunction "PC_13_7") (pintype "passive"))
    )
    (net (code "100") (name "unconnected-(U4-PD_00-Pad81)") (class "Default")
      (node (ref "U4") (pin "81") (pinfunction "PD_00_81") (pintype "passive"))
    )
    (net (code "101") (name "unconnected-(U4-PD_01-Pad82)") (class "Default")
      (node (ref "U4") (pin "82") (pinfunction "PD_01_82") (pintype "passive"))
    )
    (net (code "102") (name "unconnected-(U4-PD_02-Pad83)") (class "Default")
      (node (ref "U4") (pin "83") (pinfunction "PD_02_83") (pintype "passive"))
    )
    (net (code "103") (name "unconnected-(U4-PD_03-Pad84)") (class "Default")
      (node (ref "U4") (pin "84") (pinfunction "PD_03_84") (pintype "passive"))
    )
    (net (code "104") (name "unconnected-(U4-PD_04-Pad85)") (class "Default")
      (node (ref "U4") (pin "85") (pinfunction "PD_04_85") (pintype "passive"))
    )
    (net (code "105") (name "unconnected-(U4-PD_05-Pad86)") (class "Default")
      (node (ref "U4") (pin "86") (pinfunction "PD_05_86") (pintype "passive"))
    )
    (net (code "106") (name "unconnected-(U4-PD_06-Pad87)") (class "Default")
      (node (ref "U4") (pin "87") (pinfunction "PD_06_87") (pintype "passive"))
    )
    (net (code "107") (name "unconnected-(U4-PD_07-Pad88)") (class "Default")
      (node (ref "U4") (pin "88") (pinfunction "PD_07_88") (pintype "passive"))
    )
    (net (code "108") (name "unconnected-(U4-PE_00-Pad97)") (class "Default")
      (node (ref "U4") (pin "97") (pinfunction "PE_00_97") (pintype "passive"))
    )
    (net (code "109") (name "unconnected-(U4-PE_01-Pad98)") (class "Default")
      (node (ref "U4") (pin "98") (pinfunction "PE_01_98") (pintype "passive"))
    )
    (net (code "110") (name "unconnected-(U4-PE_04-Pad3)") (class "Default")
      (node (ref "U4") (pin "3") (pinfunction "PE_04_3") (pintype "passive"))
    )
    (net (code "111") (name "unconnected-(U4-PE_05-Pad4)") (class "Default")
      (node (ref "U4") (pin "4") (pinfunction "PE_05_4") (pintype "passive"))
    )
    (net (code "112") (name "unconnected-(U4-PE_06-Pad5)") (class "Default")
      (node (ref "U4") (pin "5") (pinfunction "PE_06_5") (pintype "passive"))
    )
    (net (code "113") (name "unconnected-(U6-S-Pad8)") (class "Default")
      (node (ref "U6") (pin "8") (pinfunction "S_8") (pintype "input+no_connect"))
    )
    (net (code "114") (name "unconnected-(U6-SHDN-Pad5)") (class "Default")
      (node (ref "U6") (pin "5") (pinfunction "SHDN_5") (pintype "input+no_connect"))
    )
  )
)
